# Covers.net
KiCad netlist of a schematic drawn in EAGLE
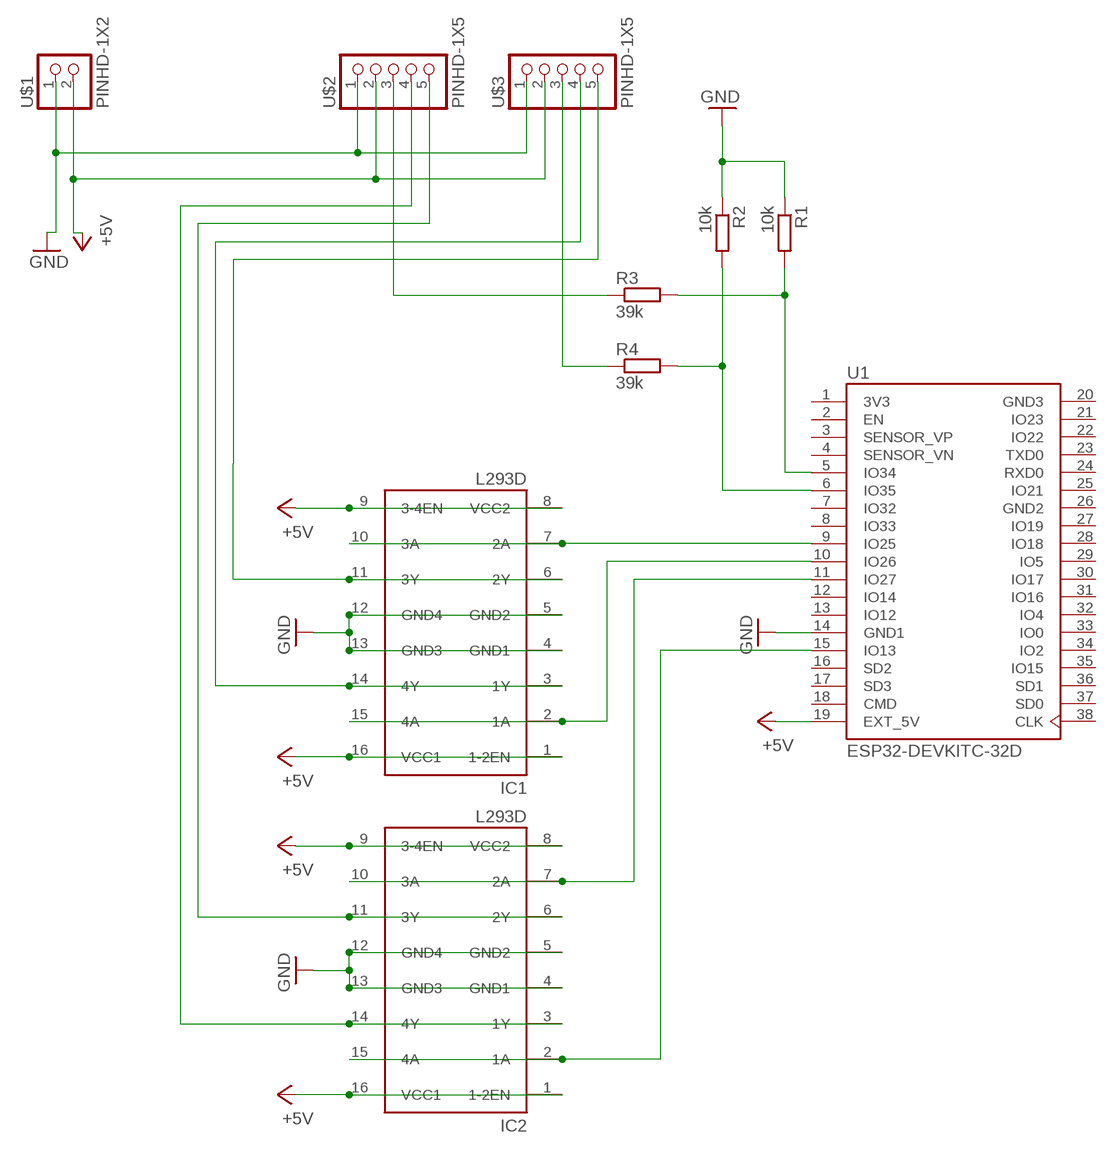
[diagram p0: schematic, sheet 1]

(export (version "E")
  (design (tool "Eeschema 10.0.6"))
  (components
    (comp (ref "IC1")
      (value "L293D")
      (footprint "eagle-import:DIL16")
      (libsource (lib "eagle-import") (part "L293D"))
    )
    (comp (ref "IC2")
      (value "L293D")
      (footprint "eagle-import:DIL16")
      (libsource (lib "eagle-import") (part "L293D"))
    )
    (comp (ref "R1")
      (value "10k")
      (footprint "eagle-import:0207_10")
      (libsource (lib "eagle-import") (part "R-EU_0207/10"))
    )
    (comp (ref "R2")
      (value "10k")
      (footprint "eagle-import:0207_10")
      (libsource (lib "eagle-import") (part "R-EU_0207/10"))
    )
    (comp (ref "R3")
      (value "39k")
      (footprint "eagle-import:0207_10")
      (libsource (lib "eagle-import") (part "R-EU_0207/10"))
    )
    (comp (ref "R4")
      (value "39k")
      (footprint "eagle-import:0207_10")
      (libsource (lib "eagle-import") (part "R-EU_0207/10"))
    )
    (comp (ref "U$1")
      (value "PINHD-1X2")
      (footprint "eagle-import:1X02")
      (libsource (lib "eagle-import") (part "PINHD-1X2"))
    )
    (comp (ref "U$2")
      (value "PINHD-1X5")
      (footprint "eagle-import:1X05")
      (libsource (lib "eagle-import") (part "PINHD-1X5"))
    )
    (comp (ref "U$3")
      (value "PINHD-1X5")
      (footprint "eagle-import:1X05")
      (libsource (lib "eagle-import") (part "PINHD-1X5"))
    )
    (comp (ref "U1")
      (value "ESP32-DEVKITC-32D")
      (footprint "eagle-import:MODULE_ESP32-DEVKITC-32D")
      (fields (field (name "MF") "Espressif Systems"))
      (libsource (lib "eagle-import") (part "ESP32-DEVKITC-32D"))
    )
  )
  (nets
    (net (code "1") (name "+5V") (class "Default")
      (node (ref "IC1") (pin "1") (pinfunction "1-2EN_1") (pintype "input"))
      (node (ref "IC1") (pin "16") (pinfunction "VCC1_16") (pintype "power_in"))
      (node (ref "IC1") (pin "8") (pinfunction "VCC2_8") (pintype "power_in"))
      (node (ref "IC1") (pin "9") (pinfunction "3-4EN_9") (pintype "input"))
      (node (ref "IC2") (pin "1") (pinfunction "1-2EN_1") (pintype "input"))
      (node (ref "IC2") (pin "16") (pinfunction "VCC1_16") (pintype "power_in"))
      (node (ref "IC2") (pin "8") (pinfunction "VCC2_8") (pintype "power_in"))
      (node (ref "IC2") (pin "9") (pinfunction "3-4EN_9") (pintype "input"))
      (node (ref "U$1") (pin "2") (pinfunction "2_2") (pintype "passive"))
      (node (ref "U$2") (pin "2") (pinfunction "2_2") (pintype "passive"))
      (node (ref "U$3") (pin "2") (pinfunction "2_2") (pintype "passive"))
      (node (ref "U1") (pin "19") (pinfunction "EXT_5V_19") (pintype "power_in"))
    )
    (net (code "2") (name "/3V3") (class "Default")
      (node (ref "U1") (pin "1") (pinfunction "3V3_1") (pintype "power_in"))
    )
    (net (code "3") (name "/GND2") (class "Default")
      (node (ref "U1") (pin "26") (pinfunction "GND2_26") (pintype "power_in"))
    )
    (net (code "4") (name "/GND3") (class "Default")
      (node (ref "U1") (pin "20") (pinfunction "GND3_20") (pintype "power_in"))
    )
    (net (code "5") (name "GND") (class "Default")
      (node (ref "IC1") (pin "12") (pinfunction "GND4_12") (pintype "power_in"))
      (node (ref "IC1") (pin "13") (pinfunction "GND3_13") (pintype "power_in"))
      (node (ref "IC1") (pin "4") (pinfunction "GND1_4") (pintype "power_in"))
      (node (ref "IC1") (pin "5") (pinfunction "GND2_5") (pintype "power_in"))
      (node (ref "IC2") (pin "12") (pinfunction "GND4_12") (pintype "power_in"))
      (node (ref "IC2") (pin "13") (pinfunction "GND3_13") (pintype "power_in"))
      (node (ref "IC2") (pin "4") (pinfunction "GND1_4") (pintype "power_in"))
      (node (ref "IC2") (pin "5") (pinfunction "GND2_5") (pintype "power_in"))
      (node (ref "R1") (pin "1") (pinfunction "1_1") (pintype "passive"))
      (node (ref "R2") (pin "1") (pinfunction "1_1") (pintype "passive"))
      (node (ref "U$1") (pin "1") (pinfunction "1_1") (pintype "passive"))
      (node (ref "U$2") (pin "1") (pinfunction "1_1") (pintype "passive"))
      (node (ref "U$3") (pin "1") (pinfunction "1_1") (pintype "passive"))
      (node (ref "U1") (pin "14") (pinfunction "GND1_14") (pintype "power_in"))
    )
    (net (code "6") (name "Net-(IC1-1A)") (class "Default")
      (node (ref "IC1") (pin "15") (pinfunction "4A_15") (pintype "input"))
      (node (ref "IC1") (pin "2") (pinfunction "1A_2") (pintype "input"))
      (node (ref "U1") (pin "10") (pinfunction "IO26_10") (pintype "bidirectional"))
    )
    (net (code "7") (name "Net-(IC1-1Y)") (class "Default")
      (node (ref "IC1") (pin "14") (pinfunction "4Y_14") (pintype "output"))
      (node (ref "IC1") (pin "3") (pinfunction "1Y_3") (pintype "output"))
      (node (ref "U$3") (pin "4") (pinfunction "4_4") (pintype "passive"))
    )
    (net (code "8") (name "Net-(IC1-2A)") (class "Default")
      (node (ref "IC1") (pin "10") (pinfunction "3A_10") (pintype "input"))
      (node (ref "IC1") (pin "7") (pinfunction "2A_7") (pintype "input"))
      (node (ref "U1") (pin "9") (pinfunction "IO25_9") (pintype "bidirectional"))
    )
    (net (code "9") (name "Net-(IC1-2Y)") (class "Default")
      (node (ref "IC1") (pin "11") (pinfunction "3Y_11") (pintype "output"))
      (node (ref "IC1") (pin "6") (pinfunction "2Y_6") (pintype "output"))
      (node (ref "U$3") (pin "5") (pinfunction "5_5") (pintype "passive"))
    )
    (net (code "10") (name "Net-(IC2-1A)") (class "Default")
      (node (ref "IC2") (pin "15") (pinfunction "4A_15") (pintype "input"))
      (node (ref "IC2") (pin "2") (pinfunction "1A_2") (pintype "input"))
      (node (ref "U1") (pin "15") (pinfunction "IO13_15") (pintype "bidirectional"))
    )
    (net (code "11") (name "Net-(IC2-1Y)") (class "Default")
      (node (ref "IC2") (pin "14") (pinfunction "4Y_14") (pintype "output"))
      (node (ref "IC2") (pin "3") (pinfunction "1Y_3") (pintype "output"))
      (node (ref "U$2") (pin "4") (pinfunction "4_4") (pintype "passive"))
    )
    (net (code "12") (name "Net-(IC2-2A)") (class "Default")
      (node (ref "IC2") (pin "10") (pinfunction "3A_10") (pintype "input"))
      (node (ref "IC2") (pin "7") (pinfunction "2A_7") (pintype "input"))
      (node (ref "U1") (pin "11") (pinfunction "IO27_11") (pintype "bidirectional"))
    )
    (net (code "13") (name "Net-(IC2-2Y)") (class "Default")
      (node (ref "IC2") (pin "11") (pinfunction "3Y_11") (pintype "output"))
      (node (ref "IC2") (pin "6") (pinfunction "2Y_6") (pintype "output"))
      (node (ref "U$2") (pin "5") (pinfunction "5_5") (pintype "passive"))
    )
    (net (code "14") (name "Net-(R3-Pad1)") (class "Default")
      (node (ref "R3") (pin "1") (pinfunction "1_1") (pintype "passive"))
      (node (ref "U$2") (pin "3") (pinfunction "3_3") (pintype "passive"))
    )
    (net (code "15") (name "Net-(R4-Pad1)") (class "Default")
      (node (ref "R4") (pin "1") (pinfunction "1_1") (pintype "passive"))
      (node (ref "U$3") (pin "3") (pinfunction "3_3") (pintype "passive"))
    )
    (net (code "16") (name "Net-(U1-IO34)") (class "Default")
      (node (ref "R1") (pin "2") (pinfunction "2_2") (pintype "passive"))
      (node (ref "R3") (pin "2") (pinfunction "2_2") (pintype "passive"))
      (node (ref "U1") (pin "5") (pinfunction "IO34_5") (pintype "bidirectional"))
    )
    (net (code "17") (name "Net-(U1-IO35)") (class "Default")
      (node (ref "R2") (pin "2") (pinfunction "2_2") (pintype "passive"))
      (node (ref "R4") (pin "2") (pinfunction "2_2") (pintype "passive"))
      (node (ref "U1") (pin "6") (pinfunction "IO35_6") (pintype "bidirectional"))
    )
    (net (code "18") (name "unconnected-(U1-CLK-Pad38)") (class "Default")
      (node (ref "U1") (pin "38") (pinfunction "CLK_38") (pintype "input"))
    )
    (net (code "19") (name "unconnected-(U1-CMD-Pad18)") (class "Default")
      (node (ref "U1") (pin "18") (pinfunction "CMD_18") (pintype "bidirectional"))
    )
    (net (code "20") (name "unconnected-(U1-EN-Pad2)") (class "Default")
      (node (ref "U1") (pin "2") (pinfunction "EN_2") (pintype "input"))
    )
    (net (code "21") (name "unconnected-(U1-IO0-Pad33)") (class "Default")
      (node (ref "U1") (pin "33") (pinfunction "IO0_33") (pintype "bidirectional"))
    )
    (net (code "22") (name "unconnected-(U1-IO2-Pad34)") (class "Default")
      (node (ref "U1") (pin "34") (pinfunction "IO2_34") (pintype "bidirectional"))
    )
    (net (code "23") (name "unconnected-(U1-IO4-Pad32)") (class "Default")
      (node (ref "U1") (pin "32") (pinfunction "IO4_32") (pintype "bidirectional"))
    )
    (net (code "24") (name "unconnected-(U1-IO5-Pad29)") (class "Default")
      (node (ref "U1") (pin "29") (pinfunction "IO5_29") (pintype "bidirectional"))
    )
    (net (code "25") (name "unconnected-(U1-IO12-Pad13)") (class "Default")
      (node (ref "U1") (pin "13") (pinfunction "IO12_13") (pintype "bidirectional"))
    )
    (net (code "26") (name "unconnected-(U1-IO14-Pad12)") (class "Default")
      (node (ref "U1") (pin "12") (pinfunction "IO14_12") (pintype "bidirectional"))
    )
    (net (code "27") (name "unconnected-(U1-IO15-Pad35)") (class "Default")
      (node (ref "U1") (pin "35") (pinfunction "IO15_35") (pintype "bidirectional"))
    )
    (net (code "28") (name "unconnected-(U1-IO16-Pad31)") (class "Default")
      (node (ref "U1") (pin "31") (pinfunction "IO16_31") (pintype "bidirectional"))
    )
    (net (code "29") (name "unconnected-(U1-IO17-Pad30)") (class "Default")
      (node (ref "U1") (pin "30") (pinfunction "IO17_30") (pintype "bidirectional"))
    )
    (net (code "30") (name "unconnected-(U1-IO18-Pad28)") (class "Default")
      (node (ref "U1") (pin "28") (pinfunction "IO18_28") (pintype "bidirectional"))
    )
    (net (code "31") (name "unconnected-(U1-IO19-Pad27)") (class "Default")
      (node (ref "U1") (pin "27") (pinfunction "IO19_27") (pintype "bidirectional"))
    )
    (net (code "32") (name "unconnected-(U1-IO21-Pad25)") (class "Default")
      (node (ref "U1") (pin "25") (pinfunction "IO21_25") (pintype "bidirectional"))
    )
    (net (code "33") (name "unconnected-(U1-IO22-Pad22)") (class "Default")
      (node (ref "U1") (pin "22") (pinfunction "IO22_22") (pintype "bidirectional"))
    )
    (net (code "34") (name "unconnected-(U1-IO23-Pad21)") (class "Default")
      (node (ref "U1") (pin "21") (pinfunction "IO23_21") (pintype "bidirectional"))
    )
    (net (code "35") (name "unconnected-(U1-IO32-Pad7)") (class "Default")
      (node (ref "U1") (pin "7") (pinfunction "IO32_7") (pintype "bidirectional"))
    )
    (net (code "36") (name "unconnected-(U1-IO33-Pad8)") (class "Default")
      (node (ref "U1") (pin "8") (pinfunction "IO33_8") (pintype "bidirectional"))
    )
    (net (code "37") (name "unconnected-(U1-RXD0-Pad24)") (class "Default")
      (node (ref "U1") (pin "24") (pinfunction "RXD0_24") (pintype "input"))
    )
    (net (code "38") (name "unconnected-(U1-SD0-Pad37)") (class "Default")
      (node (ref "U1") (pin "37") (pinfunction "SD0_37") (pintype "bidirectional"))
    )
    (net (code "39") (name "unconnected-(U1-SD1-Pad36)") (class "Default")
      (node (ref "U1") (pin "36") (pinfunction "SD1_36") (pintype "bidirectional"))
    )
    (net (code "40") (name "unconnected-(U1-SD2-Pad16)") (class "Default")
      (node (ref "U1") (pin "16") (pinfunction "SD2_16") (pintype "bidirectional"))
    )
    (net (code "41") (name "unconnected-(U1-SD3-Pad17)") (class "Default")
      (node (ref "U1") (pin "17") (pinfunction "SD3_17") (pintype "bidirectional"))
    )
    (net (code "42") (name "unconnected-(U1-SENSOR_VN-Pad4)") (class "Default")
      (node (ref "U1") (pin "4") (pinfunction "SENSOR_VN_4") (pintype "input"))
    )
    (net (code "43") (name "unconnected-(U1-SENSOR_VP-Pad3)") (class "Default")
      (node (ref "U1") (pin "3") (pinfunction "SENSOR_VP_3") (pintype "input"))
    )
    (net (code "44") (name "unconnected-(U1-TXD0-Pad23)") (class "Default")
      (node (ref "U1") (pin "23") (pinfunction "TXD0_23") (pintype "output"))
    )
  )
)
